# Sheet1.net
KiCad netlist of a schematic drawn in Altium Designer
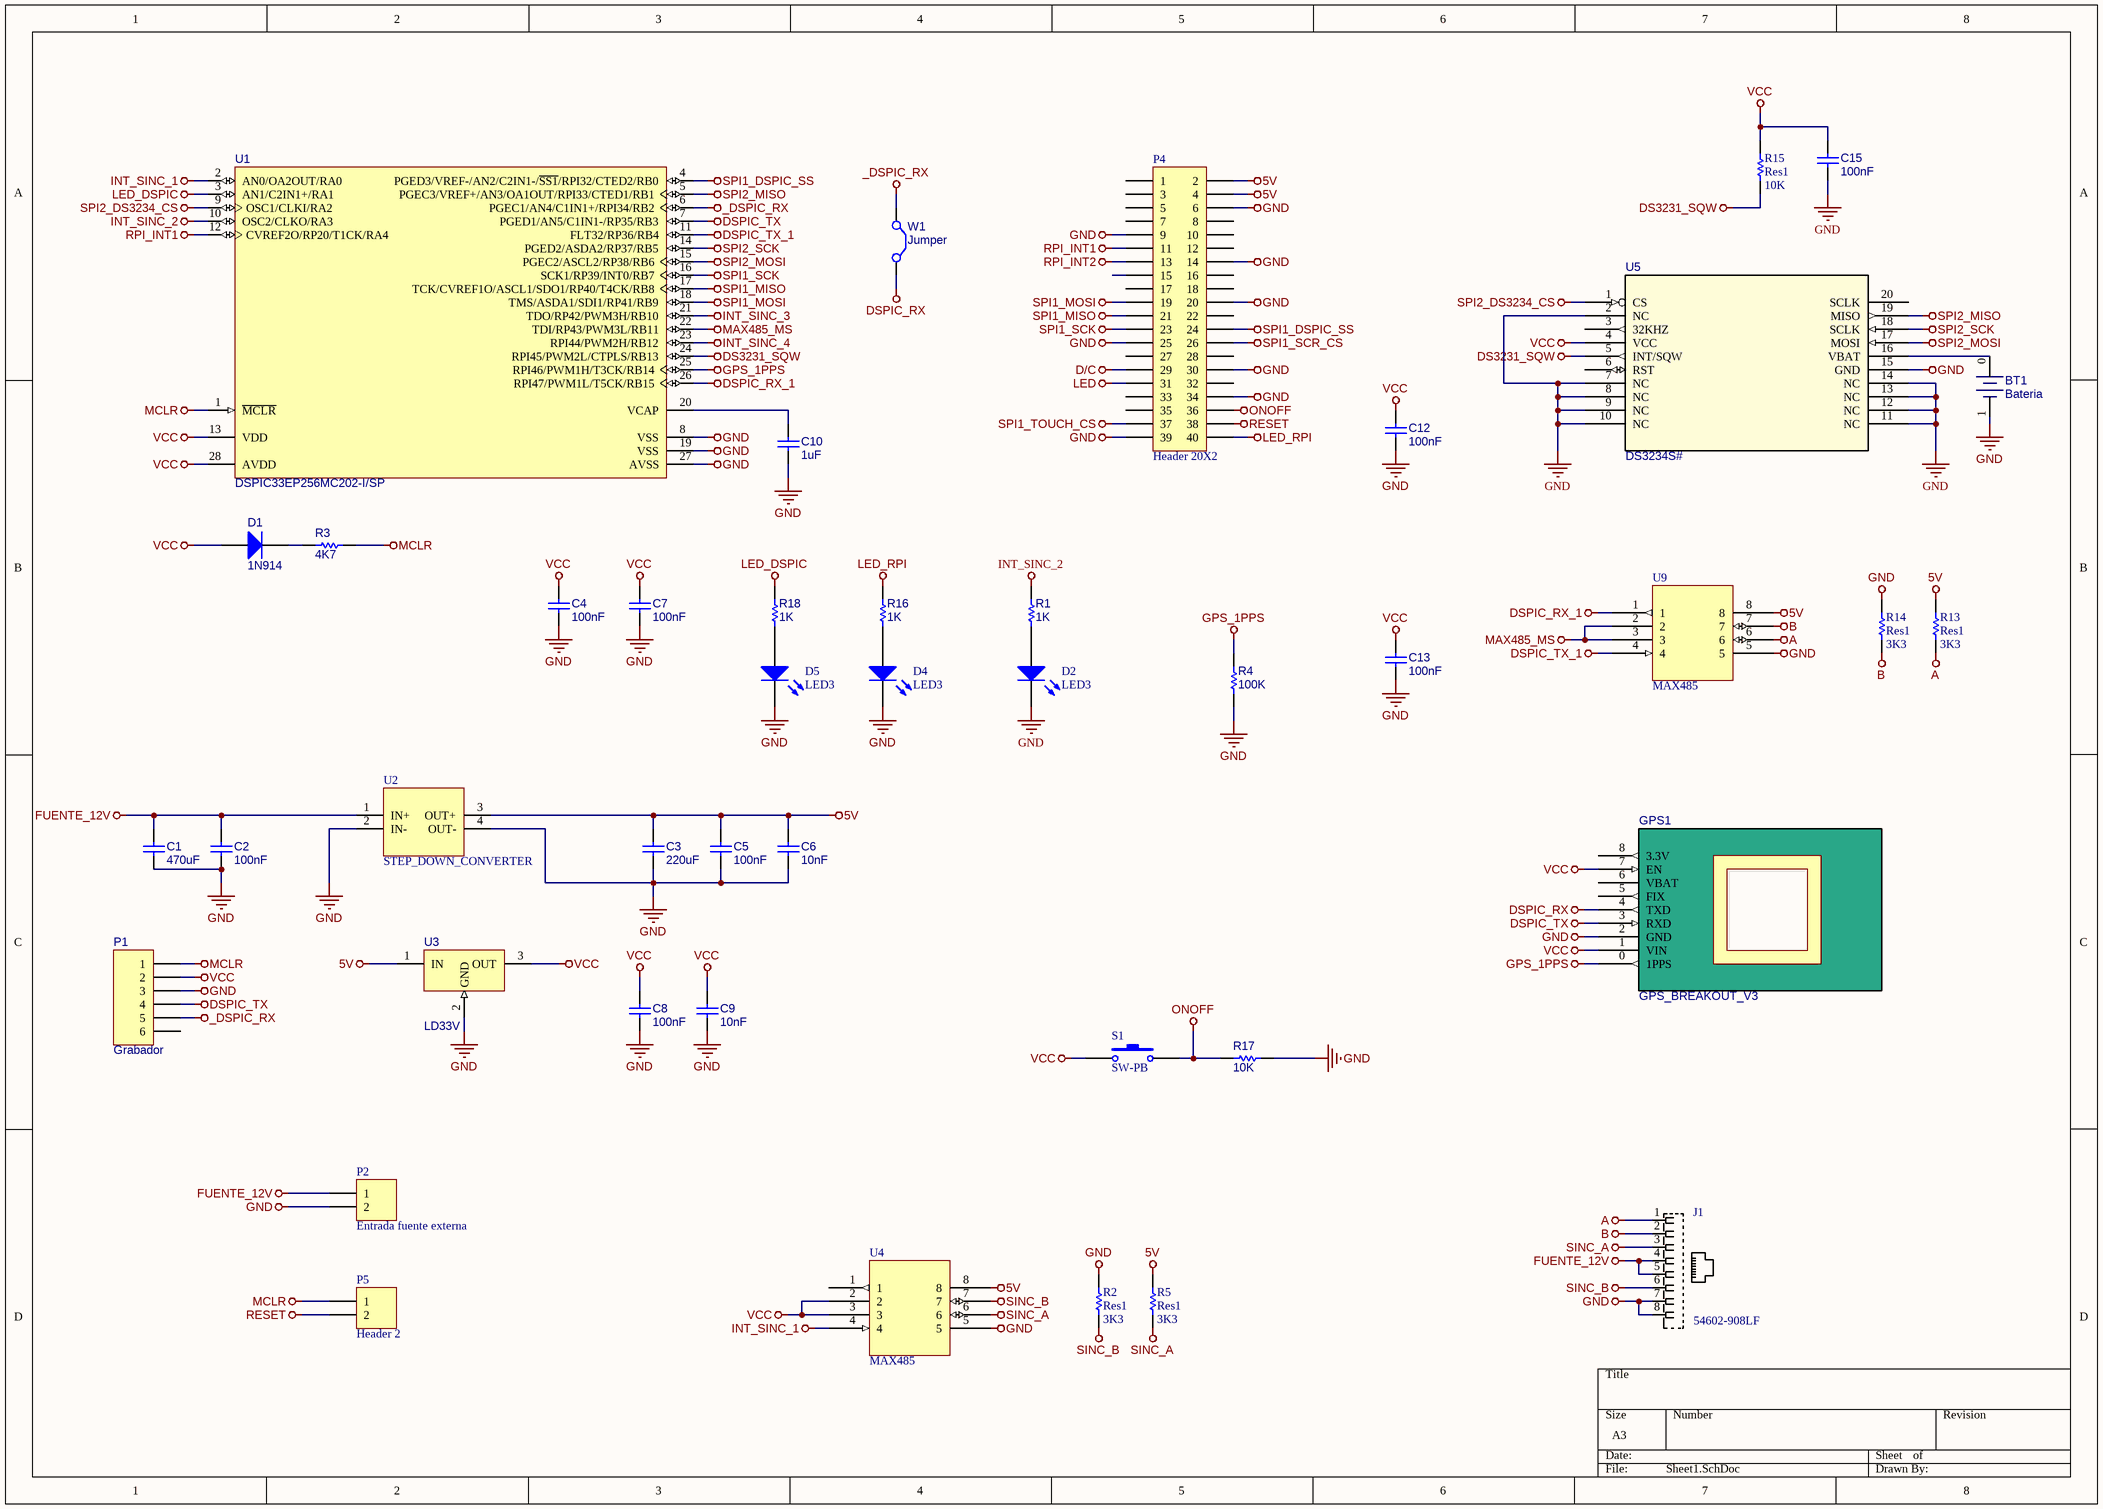
[diagram p0: Sheet1.SchDoc]

(export (version "E")
  (design (tool "Eeschema 10.0.6"))
  (components
    (comp (ref "BT1")
      (value "Bateria")
      (footprint "Bateria-DS1307")
      (libsource (lib "LibreriaRSA") (part "BateriaDS1307"))
    )
    (comp (ref "C1")
      (value "470uF")
      (footprint "C100UFB")
      (description "Capacitor")
      (fields (field (name "Comment") "Cap") (field (name "PUBLISHER") "Altium Limited"))
      (libsource (lib "Miscellaneous Devices") (part "Cap"))
    )
    (comp (ref "C2")
      (value "100nF")
      (footprint "RAD0.2")
      (description "Capacitor")
      (fields (field (name "Comment") "Cap") (field (name "PUBLISHER") "Altium Limited"))
      (libsource (lib "Miscellaneous Devices") (part "Cap"))
    )
    (comp (ref "C3")
      (value "220uF")
      (footprint "C100UFB")
      (description "Capacitor")
      (fields (field (name "Comment") "Cap") (field (name "PUBLISHER") "Altium Limited"))
      (libsource (lib "Miscellaneous Devices") (part "Cap"))
    )
    (comp (ref "C4")
      (value "100nF")
      (footprint "RAD0.2")
      (description "Capacitor")
      (fields (field (name "Comment") "Cap") (field (name "PUBLISHER") "Altium Limited"))
      (libsource (lib "Miscellaneous Devices") (part "Cap"))
    )
    (comp (ref "C5")
      (value "100nF")
      (footprint "RAD0.2")
      (description "Capacitor")
      (fields (field (name "Comment") "Cap") (field (name "PUBLISHER") "Altium Limited"))
      (libsource (lib "Miscellaneous Devices") (part "Cap"))
    )
    (comp (ref "C6")
      (value "10nF")
      (footprint "RAD0.2")
      (description "Capacitor")
      (fields (field (name "Comment") "Cap") (field (name "PUBLISHER") "Altium Limited"))
      (libsource (lib "Miscellaneous Devices") (part "Cap"))
    )
    (comp (ref "C7")
      (value "100nF")
      (footprint "RAD0.2")
      (description "Capacitor")
      (fields (field (name "Comment") "Cap") (field (name "PUBLISHER") "Altium Limited"))
      (libsource (lib "Miscellaneous Devices") (part "Cap"))
    )
    (comp (ref "C8")
      (value "100nF")
      (footprint "RAD0.2")
      (description "Capacitor")
      (fields (field (name "Comment") "Cap") (field (name "PUBLISHER") "Altium Limited"))
      (libsource (lib "Miscellaneous Devices") (part "Cap"))
    )
    (comp (ref "C9")
      (value "10nF")
      (footprint "RAD0.2")
      (description "Capacitor")
      (fields (field (name "Comment") "Cap") (field (name "PUBLISHER") "Altium Limited"))
      (libsource (lib "Miscellaneous Devices") (part "Cap"))
    )
    (comp (ref "C10")
      (value "1uF")
      (footprint "RAD0.2")
      (description "Capacitor")
      (fields (field (name "Comment") "Cap") (field (name "PUBLISHER") "Altium Limited"))
      (libsource (lib "Miscellaneous Devices") (part "Cap"))
    )
    (comp (ref "C12")
      (value "100nF")
      (footprint "RAD0.2")
      (description "Capacitor")
      (fields (field (name "Comment") "Cap") (field (name "PUBLISHER") "Altium Limited"))
      (libsource (lib "Miscellaneous Devices") (part "Cap"))
    )
    (comp (ref "C13")
      (value "100nF")
      (footprint "RAD0.2")
      (description "Capacitor")
      (fields (field (name "Comment") "Cap") (field (name "PUBLISHER") "Altium Limited"))
      (libsource (lib "Miscellaneous Devices") (part "Cap"))
    )
    (comp (ref "C15")
      (value "100nF")
      (footprint "RAD0.2")
      (description "Capacitor")
      (fields (field (name "Comment") "Cap") (field (name "PUBLISHER") "Altium Limited"))
      (libsource (lib "Miscellaneous Devices") (part "Cap"))
    )
    (comp (ref "D1")
      (value "1N914")
      (footprint "DO-35")
      (description "High Conductance Fast Diode")
      (fields (field (name "PUBLISHER") "Altium Limited"))
      (libsource (lib "Miscellaneous Devices") (part "Diode 1N914"))
    )
    (comp (ref "D2")
      (value "LED3")
      (footprint "PcbLib1:Led_Green")
      (description "Typical BLUE SiC LED")
      (fields (field (name "PUBLISHER") "Altium Limited"))
      (libsource (lib "Miscellaneous Devices") (part "LED3"))
    )
    (comp (ref "D4")
      (value "LED3")
      (footprint "PcbLib1:Led_Green")
      (description "Typical BLUE SiC LED")
      (fields (field (name "PUBLISHER") "Altium Limited"))
      (libsource (lib "Miscellaneous Devices") (part "LED3"))
    )
    (comp (ref "D5")
      (value "LED3")
      (footprint "PcbLib1:Led_Green")
      (description "Typical BLUE SiC LED")
      (fields (field (name "PUBLISHER") "Altium Limited"))
      (libsource (lib "Miscellaneous Devices") (part "LED3"))
    )
    (comp (ref "GPS1")
      (value "GPS_BREAKOUT_V3")
      (footprint "GPS_BREAKOUT_V3")
      (libsource (lib "Micelaneos") (part "GPS_BREAKOUT_V3"))
    )
    (comp (ref "J1")
      (value "54602-908LF")
      (footprint "*AMPHENOL_54602-908LF")
      (description "Jack Modular Connector 8p8c _RJ45, Ethernet_ 90Â° Angle _Right_ Unshielded Cat3")
      (fields (field (name "DIGI-KEY_PART_NUMBER") "609-1046-ND") (field (name "MF") "Amphenol ICC"))
      (libsource (lib "54602-908LF") (part "54602-908LF"))
    )
    (comp (ref "P1")
      (value "Grabador")
      (footprint "HDR1X6")
      (description "Header, 6-Pin")
      (fields (field (name "PUBLISHER") "Altium Limited"))
      (libsource (lib "Miscellaneous Connectors") (part "Header 6"))
    )
    (comp (ref "P2")
      (value "Entrada fuente externa")
      (footprint "MOLEX-2")
      (description "Header, 2-Pin")
      (fields (field (name "PUBLISHER") "Altium Limited"))
      (libsource (lib "Miscellaneous Connectors") (part "Header 2"))
    )
    (comp (ref "P4")
      (value "Header 20X2")
      (footprint "Miscellaneous Connectors_3D:HDR2X20")
      (description "Header, 20-Pin, Dual row")
      (fields (field (name "PUBLISHER") "Altium Limited"))
      (libsource (lib "Miscellaneous Connectors") (part "Header 20X2"))
    )
    (comp (ref "P5")
      (value "Header 2")
      (footprint "Header 1X2")
      (description "Header, 2-Pin")
      (fields (field (name "PUBLISHER") "Altium Limited"))
      (libsource (lib "Miscellaneous Connectors") (part "Header 2"))
    )
    (comp (ref "R1")
      (value "1K")
      (footprint "PcbLib1:AXIAL-0.3 RES-1/4W")
      (description "Resistor")
      (fields (field (name "Comment") "Res1") (field (name "PUBLISHER") "Altium Limited"))
      (libsource (lib "Miscellaneous Devices") (part "Res1"))
    )
    (comp (ref "R2")
      (value "Res1")
      (footprint "AXIAL-0.3 RES-1/4W")
      (description "Resistor")
      (fields (field (name "ALTIUM_VALUE") "3K3") (field (name "PUBLISHER") "Altium Limited"))
      (libsource (lib "Miscellaneous Devices") (part "Res1"))
    )
    (comp (ref "R3")
      (value "4K7")
      (footprint "AXIAL-0.3")
      (description "Resistor")
      (fields (field (name "Comment") "Res1") (field (name "PUBLISHER") "Altium Limited"))
      (libsource (lib "Miscellaneous Devices") (part "Res1"))
    )
    (comp (ref "R4")
      (value "100K")
      (footprint "AXIAL-0.3")
      (description "Resistor")
      (fields (field (name "Comment") "Res1") (field (name "PUBLISHER") "Altium Limited"))
      (libsource (lib "Miscellaneous Devices") (part "Res1"))
    )
    (comp (ref "R5")
      (value "Res1")
      (footprint "AXIAL-0.3 RES-1/4W")
      (description "Resistor")
      (fields (field (name "ALTIUM_VALUE") "3K3") (field (name "PUBLISHER") "Altium Limited"))
      (libsource (lib "Miscellaneous Devices") (part "Res1"))
    )
    (comp (ref "R13")
      (value "Res1")
      (footprint "AXIAL-0.3")
      (description "Resistor")
      (fields (field (name "ALTIUM_VALUE") "3K3") (field (name "PUBLISHER") "Altium Limited"))
      (libsource (lib "Miscellaneous Devices") (part "Res1"))
    )
    (comp (ref "R14")
      (value "Res1")
      (footprint "AXIAL-0.3")
      (description "Resistor")
      (fields (field (name "ALTIUM_VALUE") "3K3") (field (name "PUBLISHER") "Altium Limited"))
      (libsource (lib "Miscellaneous Devices") (part "Res1"))
    )
    (comp (ref "R15")
      (value "Res1")
      (footprint "AXIAL-0.3")
      (description "Resistor")
      (fields (field (name "ALTIUM_VALUE") "10K") (field (name "PUBLISHER") "Altium Limited"))
      (libsource (lib "Miscellaneous Devices") (part "Res1"))
    )
    (comp (ref "R16")
      (value "1K")
      (footprint "AXIAL-0.3")
      (description "Resistor")
      (fields (field (name "Comment") "Res1") (field (name "PUBLISHER") "Altium Limited"))
      (libsource (lib "Miscellaneous Devices") (part "Res1"))
    )
    (comp (ref "R17")
      (value "10K")
      (footprint "AXIAL-0.3")
      (description "Resistor")
      (fields (field (name "Comment") "Res1") (field (name "PUBLISHER") "Altium Limited"))
      (libsource (lib "Miscellaneous Devices") (part "Res1"))
    )
    (comp (ref "R18")
      (value "1K")
      (footprint "AXIAL-0.3")
      (description "Resistor")
      (fields (field (name "Comment") "Res1") (field (name "PUBLISHER") "Altium Limited"))
      (libsource (lib "Miscellaneous Devices") (part "Res1"))
    )
    (comp (ref "S1")
      (value "SW-PB")
      (footprint "PULSA4")
      (description "Switch")
      (fields (field (name "PUBLISHER") "Altium Limited"))
      (libsource (lib "Miscellaneous Devices") (part "SW-PB"))
    )
    (comp (ref "U1")
      (value "DSPIC33EP256MC202-I/SP")
      (footprint "MCHP-SPDIP-SP28")
      (fields (field (name "MANUFACTURER") "Microchip"))
      (libsource (lib "Microchip dsPIC33E") (part "DSPIC33EP256MC202-I/SP"))
    )
    (comp (ref "U2")
      (value "STEP_DOWN_CONVERTER")
      (footprint "STEP_DOWN_CONVERTER")
      (libsource (lib "Micelaneos") (part "STEP_DOWN_CONVERTER"))
    )
    (comp (ref "U3") (value "LD33V") (footprint "SOT-223") (libsource (lib "LibreriaRSA") (part "LD33V")))
    (comp (ref "U4")
      (value "MAX485")
      (footprint "DIP794W47P254L991H457Q8")
      (libsource (lib "Integrados") (part "MAX485"))
    )
    (comp (ref "U5")
      (value "DS3234S#")
      (footprint "21-0042B_20")
      (description "No Description Available")
      (fields (field (name "COPYRIGHT") "Copyright (C) 2018 Accelerated Designs. All rights reserved"))
      (libsource (lib "DS3234S") (part "DS3234S#"))
    )
    (comp (ref "U9")
      (value "MAX485")
      (footprint "DIP794W47P254L991H457Q8")
      (libsource (lib "Integrados") (part "MAX485"))
    )
    (comp (ref "W1")
      (value "Jumper")
      (footprint "SIP-2")
      (description "Jumper Wire")
      (fields (field (name "PUBLISHER") "Altium Limited"))
      (libsource (lib "Miscellaneous Devices") (part "Jumper"))
    )
  )
  (nets
    (net (code "1") (name "5V") (class "Default")
      (node (ref "C3") (pin "1") (pinfunction "1_1") (pintype "passive"))
      (node (ref "C5") (pin "1") (pinfunction "1_1") (pintype "passive"))
      (node (ref "C6") (pin "1") (pinfunction "1_1") (pintype "passive"))
      (node (ref "P4") (pin "2") (pinfunction "2_2") (pintype "passive"))
      (node (ref "P4") (pin "4") (pinfunction "4_4") (pintype "passive"))
      (node (ref "R13") (pin "2") (pinfunction "2_2") (pintype "passive"))
      (node (ref "R5") (pin "2") (pinfunction "2_2") (pintype "passive"))
      (node (ref "U2") (pin "3") (pinfunction "OUT+_3") (pintype "passive"))
      (node (ref "U3") (pin "1") (pinfunction "IN_1") (pintype "power_in"))
      (node (ref "U4") (pin "8") (pinfunction "8_8") (pintype "power_in"))
      (node (ref "U9") (pin "8") (pinfunction "8_8") (pintype "power_in"))
    )
    (net (code "2") (name "A") (class "Default")
      (node (ref "J1") (pin "1") (pinfunction "1_1") (pintype "passive"))
      (node (ref "R13") (pin "1") (pinfunction "1_1") (pintype "passive"))
      (node (ref "U9") (pin "6") (pinfunction "6_6") (pintype "bidirectional"))
    )
    (net (code "3") (name "B") (class "Default")
      (node (ref "J1") (pin "2") (pinfunction "2_2") (pintype "passive"))
      (node (ref "R14") (pin "1") (pinfunction "1_1") (pintype "passive"))
      (node (ref "U9") (pin "7") (pinfunction "7_7") (pintype "bidirectional"))
    )
    (net (code "4") (name "DS3231_SQW") (class "Default")
      (node (ref "R15") (pin "1") (pinfunction "1_1") (pintype "passive"))
      (node (ref "U1") (pin "24") (pinfunction "RPI45/PWM2L/CTPLS/RB13_24") (pintype "bidirectional"))
      (node (ref "U5") (pin "5") (pinfunction "INT/SQW_5") (pintype "output"))
    )
    (net (code "5") (name "DSPIC_RX") (class "Default")
      (node (ref "GPS1") (pin "4") (pinfunction "TXD_4") (pintype "output"))
      (node (ref "W1") (pin "2") (pinfunction "C2_2") (pintype "passive"))
    )
    (net (code "6") (name "DSPIC_RX_1") (class "Default")
      (node (ref "U1") (pin "26") (pinfunction "RPI47/PWM1L/T5CK/RB15_26") (pintype "bidirectional"))
      (node (ref "U9") (pin "1") (pinfunction "1_1") (pintype "output"))
    )
    (net (code "7") (name "DSPIC_TX") (class "Default")
      (node (ref "GPS1") (pin "3") (pinfunction "RXD_3") (pintype "input"))
      (node (ref "P1") (pin "4") (pinfunction "4_4") (pintype "passive"))
      (node (ref "U1") (pin "7") (pinfunction "PGED1/AN5/C1IN1-/RP35/RB3_7") (pintype "bidirectional"))
    )
    (net (code "8") (name "DSPIC_TX_1") (class "Default")
      (node (ref "U1") (pin "11") (pinfunction "FLT32/RP36/RB4_11") (pintype "bidirectional"))
      (node (ref "U9") (pin "4") (pinfunction "4_4") (pintype "input"))
    )
    (net (code "9") (name "D{slash}C") (class "Default")
      (node (ref "P4") (pin "29") (pinfunction "29_29") (pintype "passive"))
    )
    (net (code "10") (name "FUENTE_12V") (class "Default")
      (node (ref "C1") (pin "1") (pinfunction "1_1") (pintype "passive"))
      (node (ref "C2") (pin "1") (pinfunction "1_1") (pintype "passive"))
      (node (ref "J1") (pin "4") (pinfunction "4_4") (pintype "passive"))
      (node (ref "J1") (pin "5") (pinfunction "5_5") (pintype "passive"))
      (node (ref "P2") (pin "1") (pinfunction "1_1") (pintype "passive"))
      (node (ref "U2") (pin "1") (pinfunction "IN+_1") (pintype "passive"))
    )
    (net (code "11") (name "GND") (class "Default")
      (node (ref "BT1") (pin "1") (pinfunction "-_1") (pintype "passive"))
      (node (ref "C1") (pin "2") (pinfunction "2_2") (pintype "passive"))
      (node (ref "C10") (pin "2") (pinfunction "2_2") (pintype "passive"))
      (node (ref "C12") (pin "2") (pinfunction "2_2") (pintype "passive"))
      (node (ref "C13") (pin "2") (pinfunction "2_2") (pintype "passive"))
      (node (ref "C15") (pin "2") (pinfunction "2_2") (pintype "passive"))
      (node (ref "C2") (pin "2") (pinfunction "2_2") (pintype "passive"))
      (node (ref "C3") (pin "2") (pinfunction "2_2") (pintype "passive"))
      (node (ref "C4") (pin "2") (pinfunction "2_2") (pintype "passive"))
      (node (ref "C5") (pin "2") (pinfunction "2_2") (pintype "passive"))
      (node (ref "C6") (pin "2") (pinfunction "2_2") (pintype "passive"))
      (node (ref "C7") (pin "2") (pinfunction "2_2") (pintype "passive"))
      (node (ref "C8") (pin "2") (pinfunction "2_2") (pintype "passive"))
      (node (ref "C9") (pin "2") (pinfunction "2_2") (pintype "passive"))
      (node (ref "D2") (pin "2") (pinfunction "K_2") (pintype "passive"))
      (node (ref "D4") (pin "2") (pinfunction "K_2") (pintype "passive"))
      (node (ref "D5") (pin "2") (pinfunction "K_2") (pintype "passive"))
      (node (ref "GPS1") (pin "2") (pinfunction "GND_2") (pintype "power_in"))
      (node (ref "J1") (pin "7") (pinfunction "7_7") (pintype "passive"))
      (node (ref "J1") (pin "8") (pinfunction "8_8") (pintype "passive"))
      (node (ref "P1") (pin "3") (pinfunction "3_3") (pintype "passive"))
      (node (ref "P2") (pin "2") (pinfunction "2_2") (pintype "passive"))
      (node (ref "P4") (pin "14") (pinfunction "14_14") (pintype "passive"))
      (node (ref "P4") (pin "20") (pinfunction "20_20") (pintype "passive"))
      (node (ref "P4") (pin "25") (pinfunction "25_25") (pintype "passive"))
      (node (ref "P4") (pin "30") (pinfunction "30_30") (pintype "passive"))
      (node (ref "P4") (pin "34") (pinfunction "34_34") (pintype "passive"))
      (node (ref "P4") (pin "39") (pinfunction "39_39") (pintype "passive"))
      (node (ref "P4") (pin "6") (pinfunction "6_6") (pintype "passive"))
      (node (ref "P4") (pin "9") (pinfunction "9_9") (pintype "passive"))
      (node (ref "R14") (pin "2") (pinfunction "2_2") (pintype "passive"))
      (node (ref "R17") (pin "2") (pinfunction "2_2") (pintype "passive"))
      (node (ref "R2") (pin "2") (pinfunction "2_2") (pintype "passive"))
      (node (ref "R4") (pin "2") (pinfunction "2_2") (pintype "passive"))
      (node (ref "U1") (pin "19") (pinfunction "VSS_19") (pintype "power_in"))
      (node (ref "U1") (pin "27") (pinfunction "AVSS_27") (pintype "power_in"))
      (node (ref "U1") (pin "8") (pinfunction "VSS_8") (pintype "power_in"))
      (node (ref "U2") (pin "2") (pinfunction "IN-_2") (pintype "passive"))
      (node (ref "U2") (pin "4") (pinfunction "OUT-_4") (pintype "passive"))
      (node (ref "U3") (pin "2") (pinfunction "GND_2") (pintype "input"))
      (node (ref "U4") (pin "5") (pinfunction "5_5") (pintype "power_in"))
      (node (ref "U5") (pin "10") (pinfunction "NC_10") (pintype "passive"))
      (node (ref "U5") (pin "11") (pinfunction "NC_11") (pintype "passive"))
      (node (ref "U5") (pin "12") (pinfunction "NC_12") (pintype "passive"))
      (node (ref "U5") (pin "13") (pinfunction "NC_13") (pintype "passive"))
      (node (ref "U5") (pin "14") (pinfunction "NC_14") (pintype "passive"))
      (node (ref "U5") (pin "15") (pinfunction "GND_15") (pintype "power_in"))
      (node (ref "U5") (pin "2") (pinfunction "NC_2") (pintype "passive"))
      (node (ref "U5") (pin "7") (pinfunction "NC_7") (pintype "passive"))
      (node (ref "U5") (pin "8") (pinfunction "NC_8") (pintype "passive"))
      (node (ref "U5") (pin "9") (pinfunction "NC_9") (pintype "passive"))
      (node (ref "U9") (pin "5") (pinfunction "5_5") (pintype "power_in"))
    )
    (net (code "12") (name "GPS_1PPS") (class "Default")
      (node (ref "GPS1") (pin "0") (pinfunction "1PPS_0") (pintype "output"))
      (node (ref "R4") (pin "1") (pinfunction "1_1") (pintype "passive"))
      (node (ref "U1") (pin "25") (pinfunction "RPI46/PWM1H/T3CK/RB14_25") (pintype "bidirectional"))
    )
    (net (code "13") (name "INT_SINC_1") (class "Default")
      (node (ref "U1") (pin "2") (pinfunction "AN0/OA2OUT/RA0_2") (pintype "bidirectional"))
      (node (ref "U4") (pin "4") (pinfunction "4_4") (pintype "input"))
    )
    (net (code "14") (name "INT_SINC_2") (class "Default")
      (node (ref "R1") (pin "1") (pinfunction "1_1") (pintype "passive"))
      (node (ref "U1") (pin "10") (pinfunction "OSC2/CLKO/RA3_10") (pintype "bidirectional"))
    )
    (net (code "15") (name "INT_SINC_3") (class "Default")
      (node (ref "U1") (pin "21") (pinfunction "TDO/RP42/PWM3H/RB10_21") (pintype "bidirectional"))
    )
    (net (code "16") (name "INT_SINC_4") (class "Default")
      (node (ref "U1") (pin "23") (pinfunction "RPI44/PWM2H/RB12_23") (pintype "bidirectional"))
    )
    (net (code "17") (name "LED") (class "Default")
      (node (ref "P4") (pin "31") (pinfunction "31_31") (pintype "passive"))
    )
    (net (code "18") (name "LED_DSPIC") (class "Default")
      (node (ref "R18") (pin "1") (pinfunction "1_1") (pintype "passive"))
      (node (ref "U1") (pin "3") (pinfunction "AN1/C2IN1+/RA1_3") (pintype "bidirectional"))
    )
    (net (code "19") (name "LED_RPI") (class "Default")
      (node (ref "P4") (pin "40") (pinfunction "40_40") (pintype "passive"))
      (node (ref "R16") (pin "1") (pinfunction "1_1") (pintype "passive"))
    )
    (net (code "20") (name "MAX485_MS") (class "Default")
      (node (ref "U1") (pin "22") (pinfunction "TDI/RP43/PWM3L/RB11_22") (pintype "bidirectional"))
      (node (ref "U9") (pin "2") (pinfunction "2_2") (pintype "passive"))
      (node (ref "U9") (pin "3") (pinfunction "3_3") (pintype "passive"))
    )
    (net (code "21") (name "MCLR") (class "Default")
      (node (ref "P1") (pin "1") (pinfunction "1_1") (pintype "passive"))
      (node (ref "P5") (pin "1") (pinfunction "1_1") (pintype "passive"))
      (node (ref "R3") (pin "1") (pinfunction "1_1") (pintype "passive"))
      (node (ref "U1") (pin "1") (pinfunction "~{MCLR}_1") (pintype "input"))
    )
    (net (code "22") (name "Net-(BT1-+)") (class "Default")
      (node (ref "BT1") (pin "0") (pinfunction "+_0") (pintype "passive"))
      (node (ref "U5") (pin "16") (pinfunction "VBAT_16") (pintype "power_in"))
    )
    (net (code "23") (name "Net-(D1-K)") (class "Default")
      (node (ref "D1") (pin "2") (pinfunction "K_2") (pintype "passive"))
      (node (ref "R3") (pin "2") (pinfunction "2_2") (pintype "passive"))
    )
    (net (code "24") (name "Net-(D2-A)") (class "Default")
      (node (ref "D2") (pin "1") (pinfunction "A_1") (pintype "passive"))
      (node (ref "R1") (pin "2") (pinfunction "2_2") (pintype "passive"))
    )
    (net (code "25") (name "Net-(D4-A)") (class "Default")
      (node (ref "D4") (pin "1") (pinfunction "A_1") (pintype "passive"))
      (node (ref "R16") (pin "2") (pinfunction "2_2") (pintype "passive"))
    )
    (net (code "26") (name "Net-(D5-A)") (class "Default")
      (node (ref "D5") (pin "1") (pinfunction "A_1") (pintype "passive"))
      (node (ref "R18") (pin "2") (pinfunction "2_2") (pintype "passive"))
    )
    (net (code "27") (name "Net-(U1-VCAP)") (class "Default")
      (node (ref "C10") (pin "1") (pinfunction "1_1") (pintype "passive"))
      (node (ref "U1") (pin "20") (pinfunction "VCAP_20") (pintype "passive"))
    )
    (net (code "28") (name "ONOFF") (class "Default")
      (node (ref "P4") (pin "36") (pinfunction "36_36") (pintype "passive"))
      (node (ref "R17") (pin "1") (pinfunction "1_1") (pintype "passive"))
      (node (ref "S1") (pin "2") (pinfunction "2_2") (pintype "passive"))
    )
    (net (code "29") (name "RESET") (class "Default")
      (node (ref "P4") (pin "38") (pinfunction "38_38") (pintype "passive"))
      (node (ref "P5") (pin "2") (pinfunction "2_2") (pintype "passive"))
    )
    (net (code "30") (name "RPI_INT1") (class "Default")
      (node (ref "P4") (pin "11") (pinfunction "11_11") (pintype "passive"))
      (node (ref "U1") (pin "12") (pinfunction "CVREF2O/RP20/T1CK/RA4_12") (pintype "bidirectional"))
    )
    (net (code "31") (name "RPI_INT2") (class "Default")
      (node (ref "P4") (pin "13") (pinfunction "13_13") (pintype "passive"))
    )
    (net (code "32") (name "SINC_A") (class "Default")
      (node (ref "J1") (pin "3") (pinfunction "3_3") (pintype "passive"))
      (node (ref "R5") (pin "1") (pinfunction "1_1") (pintype "passive"))
      (node (ref "U4") (pin "6") (pinfunction "6_6") (pintype "bidirectional"))
    )
    (net (code "33") (name "SINC_B") (class "Default")
      (node (ref "J1") (pin "6") (pinfunction "6_6") (pintype "passive"))
      (node (ref "R2") (pin "1") (pinfunction "1_1") (pintype "passive"))
      (node (ref "U4") (pin "7") (pinfunction "7_7") (pintype "bidirectional"))
    )
    (net (code "34") (name "SPI1_DSPIC_SS") (class "Default")
      (node (ref "P4") (pin "24") (pinfunction "24_24") (pintype "passive"))
      (node (ref "U1") (pin "4") (pinfunction "PGED3/VREF-/AN2/C2IN1-/~{SS1}/RPI32/CTED2/RB0_4") (pintype "bidirectional"))
    )
    (net (code "35") (name "SPI1_MISO") (class "Default")
      (node (ref "P4") (pin "21") (pinfunction "21_21") (pintype "passive"))
      (node (ref "U1") (pin "17") (pinfunction "TCK/CVREF1O/ASCL1/SDO1/RP40/T4CK/RB8_17") (pintype "bidirectional"))
    )
    (net (code "36") (name "SPI1_MOSI") (class "Default")
      (node (ref "P4") (pin "19") (pinfunction "19_19") (pintype "passive"))
      (node (ref "U1") (pin "18") (pinfunction "TMS/ASDA1/SDI1/RP41/RB9_18") (pintype "bidirectional"))
    )
    (net (code "37") (name "SPI1_SCK") (class "Default")
      (node (ref "P4") (pin "23") (pinfunction "23_23") (pintype "passive"))
      (node (ref "U1") (pin "16") (pinfunction "SCK1/RP39/INT0/RB7_16") (pintype "bidirectional"))
    )
    (net (code "38") (name "SPI1_SCR_CS") (class "Default")
      (node (ref "P4") (pin "26") (pinfunction "26_26") (pintype "passive"))
    )
    (net (code "39") (name "SPI1_TOUCH_CS") (class "Default")
      (node (ref "P4") (pin "37") (pinfunction "37_37") (pintype "passive"))
    )
    (net (code "40") (name "SPI2_DS3234_CS") (class "Default")
      (node (ref "U1") (pin "9") (pinfunction "OSC1/CLKI/RA2_9") (pintype "bidirectional"))
      (node (ref "U5") (pin "1") (pinfunction "CS_1") (pintype "input"))
    )
    (net (code "41") (name "SPI2_MISO") (class "Default")
      (node (ref "U1") (pin "5") (pinfunction "PGEC3/VREF+/AN3/OA1OUT/RPI33/CTED1/RB1_5") (pintype "bidirectional"))
      (node (ref "U5") (pin "19") (pinfunction "MISO_19") (pintype "output"))
    )
    (net (code "42") (name "SPI2_MOSI") (class "Default")
      (node (ref "U1") (pin "15") (pinfunction "PGEC2/ASCL2/RP38/RB6_15") (pintype "bidirectional"))
      (node (ref "U5") (pin "17") (pinfunction "MOSI_17") (pintype "input"))
    )
    (net (code "43") (name "SPI2_SCK") (class "Default")
      (node (ref "U1") (pin "14") (pinfunction "PGED2/ASDA2/RP37/RB5_14") (pintype "bidirectional"))
      (node (ref "U5") (pin "18") (pinfunction "SCLK_18") (pintype "input"))
    )
    (net (code "44") (name "VCC") (class "Default")
      (node (ref "C12") (pin "1") (pinfunction "1_1") (pintype "passive"))
      (node (ref "C13") (pin "1") (pinfunction "1_1") (pintype "passive"))
      (node (ref "C15") (pin "1") (pinfunction "1_1") (pintype "passive"))
      (node (ref "C4") (pin "1") (pinfunction "1_1") (pintype "passive"))
      (node (ref "C7") (pin "1") (pinfunction "1_1") (pintype "passive"))
      (node (ref "C8") (pin "1") (pinfunction "1_1") (pintype "passive"))
      (node (ref "C9") (pin "1") (pinfunction "1_1") (pintype "passive"))
      (node (ref "D1") (pin "1") (pinfunction "A_1") (pintype "passive"))
      (node (ref "GPS1") (pin "1") (pinfunction "VIN_1") (pintype "power_in"))
      (node (ref "GPS1") (pin "7") (pinfunction "EN_7") (pintype "input"))
      (node (ref "P1") (pin "2") (pinfunction "2_2") (pintype "passive"))
      (node (ref "R15") (pin "2") (pinfunction "2_2") (pintype "passive"))
      (node (ref "S1") (pin "1") (pinfunction "1_1") (pintype "passive"))
      (node (ref "U1") (pin "13") (pinfunction "VDD_13") (pintype "power_in"))
      (node (ref "U1") (pin "28") (pinfunction "AVDD_28") (pintype "power_in"))
      (node (ref "U3") (pin "3") (pinfunction "OUT_3") (pintype "power_in"))
      (node (ref "U4") (pin "2") (pinfunction "2_2") (pintype "passive"))
      (node (ref "U4") (pin "3") (pinfunction "3_3") (pintype "passive"))
      (node (ref "U5") (pin "4") (pinfunction "VCC_4") (pintype "power_in"))
    )
    (net (code "45") (name "_DSPIC_RX") (class "Default")
      (node (ref "P1") (pin "5") (pinfunction "5_5") (pintype "passive"))
      (node (ref "U1") (pin "6") (pinfunction "PGEC1/AN4/C1IN1+/RPI34/RB2_6") (pintype "bidirectional"))
      (node (ref "W1") (pin "1") (pinfunction "C1_1") (pintype "passive"))
    )
    (net (code "46") (name "unconnected-(GPS1-3.3V-Pad8)") (class "Default")
      (node (ref "GPS1") (pin "8") (pinfunction "3.3V_8") (pintype "output"))
    )
    (net (code "47") (name "unconnected-(GPS1-FIX-Pad5)") (class "Default")
      (node (ref "GPS1") (pin "5") (pinfunction "FIX_5") (pintype "output"))
    )
    (net (code "48") (name "unconnected-(GPS1-VBAT-Pad6)") (class "Default")
      (node (ref "GPS1") (pin "6") (pinfunction "VBAT_6") (pintype "passive"))
    )
    (net (code "49") (name "unconnected-(P1-Pad6)") (class "Default")
      (node (ref "P1") (pin "6") (pinfunction "6_6") (pintype "passive"))
    )
    (net (code "50") (name "unconnected-(P4-Pad1)") (class "Default")
      (node (ref "P4") (pin "1") (pinfunction "1_1") (pintype "passive"))
    )
    (net (code "51") (name "unconnected-(P4-Pad3)") (class "Default")
      (node (ref "P4") (pin "3") (pinfunction "3_3") (pintype "passive"))
    )
    (net (code "52") (name "unconnected-(P4-Pad5)") (class "Default")
      (node (ref "P4") (pin "5") (pinfunction "5_5") (pintype "passive"))
    )
    (net (code "53") (name "unconnected-(P4-Pad7)") (class "Default")
      (node (ref "P4") (pin "7") (pinfunction "7_7") (pintype "passive"))
    )
    (net (code "54") (name "unconnected-(P4-Pad8)") (class "Default")
      (node (ref "P4") (pin "8") (pinfunction "8_8") (pintype "passive"))
    )
    (net (code "55") (name "unconnected-(P4-Pad10)") (class "Default")
      (node (ref "P4") (pin "10") (pinfunction "10_10") (pintype "passive"))
    )
    (net (code "56") (name "unconnected-(P4-Pad12)") (class "Default")
      (node (ref "P4") (pin "12") (pinfunction "12_12") (pintype "passive"))
    )
    (net (code "57") (name "unconnected-(P4-Pad15)") (class "Default")
      (node (ref "P4") (pin "15") (pinfunction "15_15") (pintype "passive"))
    )
    (net (code "58") (name "unconnected-(P4-Pad16)") (class "Default")
      (node (ref "P4") (pin "16") (pinfunction "16_16") (pintype "passive"))
    )
    (net (code "59") (name "unconnected-(P4-Pad17)") (class "Default")
      (node (ref "P4") (pin "17") (pinfunction "17_17") (pintype "passive"))
    )
    (net (code "60") (name "unconnected-(P4-Pad18)") (class "Default")
      (node (ref "P4") (pin "18") (pinfunction "18_18") (pintype "passive"))
    )
    (net (code "61") (name "unconnected-(P4-Pad22)") (class "Default")
      (node (ref "P4") (pin "22") (pinfunction "22_22") (pintype "passive"))
    )
    (net (code "62") (name "unconnected-(P4-Pad27)") (class "Default")
      (node (ref "P4") (pin "27") (pinfunction "27_27") (pintype "passive"))
    )
    (net (code "63") (name "unconnected-(P4-Pad28)") (class "Default")
      (node (ref "P4") (pin "28") (pinfunction "28_28") (pintype "passive"))
    )
    (net (code "64") (name "unconnected-(P4-Pad32)") (class "Default")
      (node (ref "P4") (pin "32") (pinfunction "32_32") (pintype "passive"))
    )
    (net (code "65") (name "unconnected-(P4-Pad33)") (class "Default")
      (node (ref "P4") (pin "33") (pinfunction "33_33") (pintype "passive"))
    )
    (net (code "66") (name "unconnected-(P4-Pad35)") (class "Default")
      (node (ref "P4") (pin "35") (pinfunction "35_35") (pintype "passive"))
    )
    (net (code "67") (name "unconnected-(U4-Pad1)") (class "Default")
      (node (ref "U4") (pin "1") (pinfunction "1_1") (pintype "output"))
    )
    (net (code "68") (name "unconnected-(U5-32KHZ-Pad3)") (class "Default")
      (node (ref "U5") (pin "3") (pinfunction "32KHZ_3") (pintype "output"))
    )
    (net (code "69") (name "unconnected-(U5-RST-Pad6)") (class "Default")
      (node (ref "U5") (pin "6") (pinfunction "RST_6") (pintype "bidirectional"))
    )
    (net (code "70") (name "unconnected-(U5-SCLK-Pad20)") (class "Default")
      (node (ref "U5") (pin "20") (pinfunction "SCLK_20") (pintype "passive"))
    )
  )
)
